# Schematic.net
KiCad netlist of a schematic drawn in Altium Designer
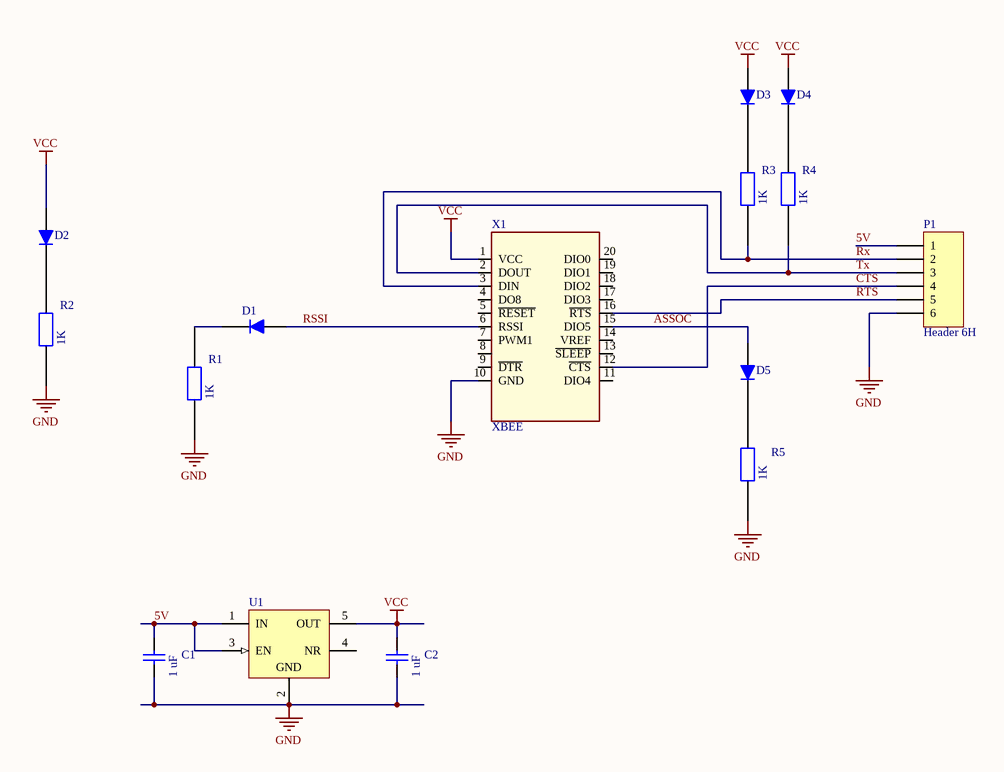
[diagram p0: Schematic.SchDoc]

(export (version "E")
  (design (tool "Eeschema 10.0.6"))
  (components
    (comp (ref "C1")
      (value "GCM188R71C105KA64D")
      (footprint "CAPC1608")
      (description "Multilayer Ceramic Capacitors MLCC - SMD/SMT 0603 1.0uF 16volts X7R 10%")
      (fields (field (name "MANUFACTURER") "Murata Electronics") (field (name "TOLERANCE") "10 %"))
      (libsource (lib "Schlib1") (part "GCM188R71C105KA64D"))
    )
    (comp (ref "C2")
      (value "GCM188R71C105KA64D")
      (footprint "CAPC1608")
      (description "Multilayer Ceramic Capacitors MLCC - SMD/SMT 0603 1.0uF 16volts X7R 10%")
      (fields (field (name "MANUFACTURER") "Murata Electronics") (field (name "TOLERANCE") "10 %"))
      (libsource (lib "Schlib1") (part "GCM188R71C105KA64D"))
    )
    (comp (ref "D1")
      (value "LTST-C191KGKT")
      (footprint "LEDC1608M_AK")
      (description "LED GREEN CLEAR 0603 SMD")
      (fields (field (name "MANUFACTURER") "Lite-On Inc."))
      (libsource (lib "Schlib1") (part "LTST-C191KGKT"))
    )
    (comp (ref "D2")
      (value "LTST-C191KGKT")
      (footprint "LEDC1608M_AK")
      (description "LED GREEN CLEAR 0603 SMD")
      (fields (field (name "MANUFACTURER") "Lite-On Inc."))
      (libsource (lib "Schlib1") (part "LTST-C191KGKT"))
    )
    (comp (ref "D3")
      (value "LTST-C191KGKT")
      (footprint "LEDC1608M_AK")
      (description "LED GREEN CLEAR 0603 SMD")
      (fields (field (name "MANUFACTURER") "Lite-On Inc."))
      (libsource (lib "Schlib1") (part "LTST-C191KGKT"))
    )
    (comp (ref "D4")
      (value "LTST-C191KGKT")
      (footprint "LEDC1608M_AK")
      (description "LED GREEN CLEAR 0603 SMD")
      (fields (field (name "MANUFACTURER") "Lite-On Inc."))
      (libsource (lib "Schlib1") (part "LTST-C191KGKT"))
    )
    (comp (ref "D5")
      (value "LTST-C191KGKT")
      (footprint "LEDC1608M_AK")
      (description "LED GREEN CLEAR 0603 SMD")
      (fields (field (name "MANUFACTURER") "Lite-On Inc."))
      (libsource (lib "Schlib1") (part "LTST-C191KGKT"))
    )
    (comp (ref "P1")
      (value "Header 6H")
      (footprint "DF13A-6P-1.25H")
      (description "Header, 6-Pin, Right Angle")
      (fields (field (name "PUBLISHER") "Altium Limited"))
      (libsource (lib "Miscellaneous Connectors") (part "Header 6H"))
    )
    (comp (ref "R1")
      (value "CR0603-FX-1001ELF")
      (footprint "RESC1608")
      (description "RES SMD 1K OHM 1% 1/10W 0603")
      (fields (field (name "MANUFACTURER") "Bourns Inc.") (field (name "TOLERANCE") "±1%"))
      (libsource (lib "Schlib1") (part "CR0603-FX-1001ELF"))
    )
    (comp (ref "R2")
      (value "CR0603-FX-1001ELF")
      (footprint "RESC1608")
      (description "RES SMD 1K OHM 1% 1/10W 0603")
      (fields (field (name "MANUFACTURER") "Bourns Inc.") (field (name "TOLERANCE") "±1%"))
      (libsource (lib "Schlib1") (part "CR0603-FX-1001ELF"))
    )
    (comp (ref "R3")
      (value "CR0603-FX-1001ELF")
      (footprint "RESC1608")
      (description "RES SMD 1K OHM 1% 1/10W 0603")
      (fields (field (name "MANUFACTURER") "Bourns Inc.") (field (name "TOLERANCE") "±1%"))
      (libsource (lib "Schlib1") (part "CR0603-FX-1001ELF"))
    )
    (comp (ref "R4")
      (value "CR0603-FX-1001ELF")
      (footprint "RESC1608")
      (description "RES SMD 1K OHM 1% 1/10W 0603")
      (fields (field (name "MANUFACTURER") "Bourns Inc.") (field (name "TOLERANCE") "±1%"))
      (libsource (lib "Schlib1") (part "CR0603-FX-1001ELF"))
    )
    (comp (ref "R5")
      (value "CR0603-FX-1001ELF")
      (footprint "RESC1608")
      (description "RES SMD 1K OHM 1% 1/10W 0603")
      (fields (field (name "MANUFACTURER") "Bourns Inc.") (field (name "TOLERANCE") "±1%"))
      (libsource (lib "Schlib1") (part "CR0603-FX-1001ELF"))
    )
    (comp (ref "U1")
      (value "V62/06626-05XE")
      (footprint "TI-DBV5_N")
      (fields (field (name "MANUFACTURER") "Texas Instruments"))
      (libsource (lib "TI Power Management Linear Regulator Single Channel LDO (400-7500mA)") (part "V62/06626-05XE"))
    )
    (comp (ref "X1") (value "XBEE") (footprint "XBEE_PRO_ANT") (libsource (lib "XBee") (part "XBEE")))
  )
  (nets
    (net (code "1") (name "/5V") (class "Default")
      (node (ref "C1") (pin "2") (pinfunction "2_2") (pintype "passive"))
      (node (ref "P1") (pin "1") (pinfunction "1_1") (pintype "passive"))
      (node (ref "U1") (pin "1") (pinfunction "IN_1") (pintype "power_in"))
      (node (ref "U1") (pin "3") (pinfunction "EN_3") (pintype "input"))
    )
    (net (code "2") (name "/ASSOC") (class "Default")
      (node (ref "D5") (pin "A") (pinfunction "A_A") (pintype "passive"))
      (node (ref "X1") (pin "15") (pinfunction "DIO5_15") (pintype "passive"))
    )
    (net (code "3") (name "/CTS") (class "Default")
      (node (ref "P1") (pin "4") (pinfunction "4_4") (pintype "passive"))
      (node (ref "X1") (pin "12") (pinfunction "~{CTS}_12") (pintype "passive"))
    )
    (net (code "4") (name "/RSSI") (class "Default")
      (node (ref "D1") (pin "A") (pinfunction "A_A") (pintype "passive"))
      (node (ref "X1") (pin "6") (pinfunction "RSSI_6") (pintype "passive"))
    )
    (net (code "5") (name "/RTS") (class "Default")
      (node (ref "P1") (pin "5") (pinfunction "5_5") (pintype "passive"))
      (node (ref "X1") (pin "16") (pinfunction "~{RTS}_16") (pintype "passive"))
    )
    (net (code "6") (name "/Rx") (class "Default")
      (node (ref "P1") (pin "2") (pinfunction "2_2") (pintype "passive"))
      (node (ref "R3") (pin "1") (pintype "passive"))
      (node (ref "X1") (pin "3") (pinfunction "DIN_3") (pintype "passive"))
    )
    (net (code "7") (name "/Tx") (class "Default")
      (node (ref "P1") (pin "3") (pinfunction "3_3") (pintype "passive"))
      (node (ref "R4") (pin "1") (pintype "passive"))
      (node (ref "X1") (pin "2") (pinfunction "DOUT_2") (pintype "passive"))
    )
    (net (code "8") (name "GND") (class "Default")
      (node (ref "C1") (pin "1") (pinfunction "1_1") (pintype "passive"))
      (node (ref "C2") (pin "1") (pinfunction "1_1") (pintype "passive"))
      (node (ref "P1") (pin "6") (pinfunction "6_6") (pintype "passive"))
      (node (ref "R1") (pin "1") (pintype "passive"))
      (node (ref "R2") (pin "1") (pintype "passive"))
      (node (ref "R5") (pin "1") (pintype "passive"))
      (node (ref "U1") (pin "2") (pinfunction "GND_2") (pintype "power_in"))
      (node (ref "X1") (pin "10") (pinfunction "GND_10") (pintype "passive"))
    )
    (net (code "9") (name "Net-(D1-PadK)") (class "Default")
      (node (ref "D1") (pin "K") (pinfunction "K_K") (pintype "passive"))
      (node (ref "R1") (pin "2") (pintype "passive"))
    )
    (net (code "10") (name "Net-(D2-PadK)") (class "Default")
      (node (ref "D2") (pin "K") (pinfunction "K_K") (pintype "passive"))
      (node (ref "R2") (pin "2") (pintype "passive"))
    )
    (net (code "11") (name "Net-(D3-PadK)") (class "Default")
      (node (ref "D3") (pin "K") (pinfunction "K_K") (pintype "passive"))
      (node (ref "R3") (pin "2") (pintype "passive"))
    )
    (net (code "12") (name "Net-(D4-PadK)") (class "Default")
      (node (ref "D4") (pin "K") (pinfunction "K_K") (pintype "passive"))
      (node (ref "R4") (pin "2") (pintype "passive"))
    )
    (net (code "13") (name "Net-(D5-PadK)") (class "Default")
      (node (ref "D5") (pin "K") (pinfunction "K_K") (pintype "passive"))
      (node (ref "R5") (pin "2") (pintype "passive"))
    )
    (net (code "14") (name "VCC") (class "Default")
      (node (ref "C2") (pin "2") (pinfunction "2_2") (pintype "passive"))
      (node (ref "D2") (pin "A") (pinfunction "A_A") (pintype "passive"))
      (node (ref "D3") (pin "A") (pinfunction "A_A") (pintype "passive"))
      (node (ref "D4") (pin "A") (pinfunction "A_A") (pintype "passive"))
      (node (ref "U1") (pin "5") (pinfunction "OUT_5") (pintype "power_in"))
      (node (ref "X1") (pin "1") (pinfunction "VCC_1") (pintype "passive"))
    )
    (net (code "15") (name "unconnected-(U1-NR-Pad4)") (class "Default")
      (node (ref "U1") (pin "4") (pinfunction "NR_4") (pintype "passive"))
    )
    (net (code "16") (name "unconnected-(X1-DIO0-Pad20)") (class "Default")
      (node (ref "X1") (pin "20") (pinfunction "DIO0_20") (pintype "passive"))
    )
    (net (code "17") (name "unconnected-(X1-DIO1-Pad19)") (class "Default")
      (node (ref "X1") (pin "19") (pinfunction "DIO1_19") (pintype "passive"))
    )
    (net (code "18") (name "unconnected-(X1-DIO2-Pad18)") (class "Default")
      (node (ref "X1") (pin "18") (pinfunction "DIO2_18") (pintype "passive"))
    )
    (net (code "19") (name "unconnected-(X1-DIO3-Pad17)") (class "Default")
      (node (ref "X1") (pin "17") (pinfunction "DIO3_17") (pintype "passive"))
    )
    (net (code "20") (name "unconnected-(X1-DIO4-Pad11)") (class "Default")
      (node (ref "X1") (pin "11") (pinfunction "DIO4_11") (pintype "passive"))
    )
    (net (code "21") (name "unconnected-(X1-DO8-Pad4)") (class "Default")
      (node (ref "X1") (pin "4") (pinfunction "DO8_4") (pintype "passive"))
    )
    (net (code "22") (name "unconnected-(X1-PWM1-Pad7)") (class "Default")
      (node (ref "X1") (pin "7") (pinfunction "PWM1_7") (pintype "passive"))
    )
    (net (code "23") (name "unconnected-(X1-Pad8)") (class "Default")
      (node (ref "X1") (pin "8") (pintype "passive"))
    )
    (net (code "24") (name "unconnected-(X1-VREF-Pad14)") (class "Default")
      (node (ref "X1") (pin "14") (pinfunction "VREF_14") (pintype "passive"))
    )
    (net (code "25") (name "unconnected-(X1-~{DTR}-Pad9)") (class "Default")
      (node (ref "X1") (pin "9") (pinfunction "~{DTR}_9") (pintype "passive"))
    )
    (net (code "26") (name "unconnected-(X1-~{RESET}-Pad5)") (class "Default")
      (node (ref "X1") (pin "5") (pinfunction "~{RESET}_5") (pintype "passive"))
    )
    (net (code "27") (name "unconnected-(X1-~{SLEEP}-Pad13)") (class "Default")
      (node (ref "X1") (pin "13") (pinfunction "~{SLEEP}_13") (pintype "passive"))
    )
  )
)
